# Cameras.net
KiCad netlist of a schematic drawn in Altium Designer
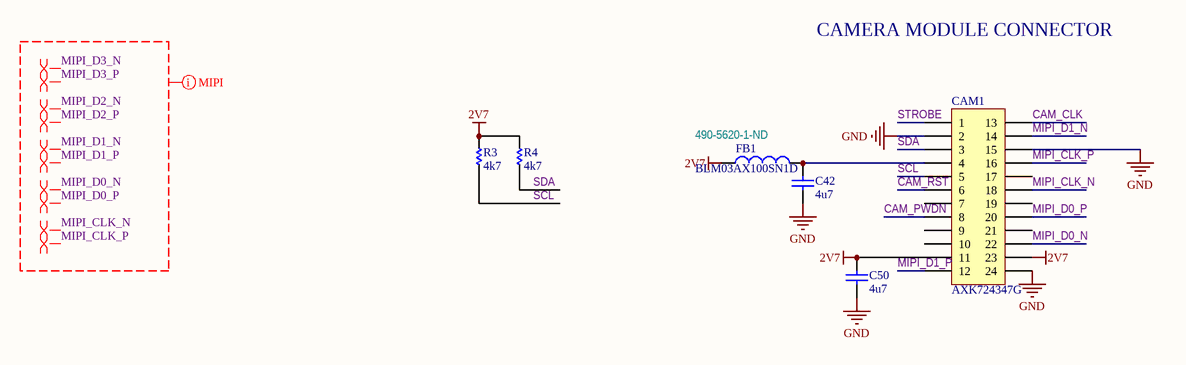
[diagram p0: Cameras.SchDoc]

(export (version "E")
  (design (tool "Eeschema 10.0.6"))
  (components
    (comp (ref "C42")
      (value "4u7")
      (footprint "CAPC1005N")
      (description "Capacitor (Semiconductor SIM Model)")
      (fields (field (name "PUBLISHER") "Altium Limited"))
      (libsource (lib "Miscellaneous Devices") (part "Cap Semi"))
    )
    (comp (ref "C50")
      (value "4u7")
      (footprint "CAPC1005N")
      (description "Capacitor (Semiconductor SIM Model)")
      (fields (field (name "PUBLISHER") "Altium Limited"))
      (libsource (lib "Miscellaneous Devices") (part "Cap Semi"))
    )
    (comp (ref "CAM1")
      (value "AXK724347G")
      (footprint "LI-OV5640-MIPI-AF")
      (description "Header, 12-Pin, Dual row")
      (fields (field (name "PUBLISHER") "Altium Limited"))
      (libsource (lib "Miscellaneous Connectors") (part "Header 12X2A"))
    )
    (comp (ref "FB1")
      (value "BLM03AX100SN1D")
      (footprint "1608[0603]")
      (description "Inductor")
      (fields
        (field (name "SUPPLIER PART NUMBER 1") "490-5620-1-ND")
        (field (name "PUBLISHER") "Altium Limited")
      )
      (libsource (lib "Miscellaneous Devices") (part "Inductor"))
    )
    (comp (ref "R3")
      (value "4k7")
      (footprint "RESC0603N")
      (description "Semiconductor Resistor")
      (fields (field (name "PUBLISHER") "Altium Limited"))
      (libsource (lib "Miscellaneous Devices") (part "Res Semi"))
    )
    (comp (ref "R4")
      (value "4k7")
      (footprint "RESC0603N")
      (description "Semiconductor Resistor")
      (fields (field (name "PUBLISHER") "Altium Limited"))
      (libsource (lib "Miscellaneous Devices") (part "Res Semi"))
    )
  )
  (nets
    (net (code "1") (name "/CAM_CLK") (class "Default")
      (node (ref "CAM1") (pin "13") (pinfunction "13_13") (pintype "passive"))
    )
    (net (code "2") (name "/CAM_PWDN") (class "Default")
      (node (ref "CAM1") (pin "8") (pinfunction "8_8") (pintype "passive"))
    )
    (net (code "3") (name "/CAM_RST") (class "Default")
      (node (ref "CAM1") (pin "6") (pinfunction "6_6") (pintype "passive"))
    )
    (net (code "4") (name "/MIPI_CLK_N") (class "Default")
      (node (ref "CAM1") (pin "18") (pinfunction "18_18") (pintype "passive"))
    )
    (net (code "5") (name "/MIPI_CLK_P") (class "Default")
      (node (ref "CAM1") (pin "16") (pinfunction "16_16") (pintype "passive"))
    )
    (net (code "6") (name "/MIPI_D0_N") (class "Default")
      (node (ref "CAM1") (pin "22") (pinfunction "22_22") (pintype "passive"))
    )
    (net (code "7") (name "/MIPI_D0_P") (class "Default")
      (node (ref "CAM1") (pin "20") (pinfunction "20_20") (pintype "passive"))
    )
    (net (code "8") (name "/MIPI_D1_N") (class "Default")
      (node (ref "CAM1") (pin "14") (pinfunction "14_14") (pintype "passive"))
    )
    (net (code "9") (name "/MIPI_D1_P") (class "Default")
      (node (ref "CAM1") (pin "12") (pinfunction "12_12") (pintype "passive"))
    )
    (net (code "14") (name "/SCL") (class "Default")
      (node (ref "CAM1") (pin "5") (pinfunction "5_5") (pintype "passive"))
      (node (ref "R3") (pin "1") (pinfunction "1_1") (pintype "passive"))
    )
    (net (code "15") (name "/SDA") (class "Default")
      (node (ref "CAM1") (pin "3") (pinfunction "3_3") (pintype "passive"))
      (node (ref "R4") (pin "1") (pinfunction "1_1") (pintype "passive"))
    )
    (net (code "16") (name "/STROBE") (class "Default")
      (node (ref "CAM1") (pin "1") (pinfunction "1_1") (pintype "passive"))
    )
    (net (code "17") (name "2V7") (class "Default")
      (node (ref "C50") (pin "2") (pinfunction "2_2") (pintype "passive"))
      (node (ref "CAM1") (pin "11") (pinfunction "11_11") (pintype "passive"))
      (node (ref "CAM1") (pin "23") (pinfunction "23_23") (pintype "passive"))
      (node (ref "FB1") (pin "1") (pinfunction "1_1") (pintype "passive"))
      (node (ref "R3") (pin "2") (pinfunction "2_2") (pintype "passive"))
      (node (ref "R4") (pin "2") (pinfunction "2_2") (pintype "passive"))
    )
    (net (code "18") (name "GND") (class "Default")
      (node (ref "C42") (pin "1") (pinfunction "1_1") (pintype "passive"))
      (node (ref "C50") (pin "1") (pinfunction "1_1") (pintype "passive"))
      (node (ref "CAM1") (pin "15") (pinfunction "15_15") (pintype "passive"))
      (node (ref "CAM1") (pin "2") (pinfunction "2_2") (pintype "passive"))
      (node (ref "CAM1") (pin "24") (pinfunction "24_24") (pintype "passive"))
    )
    (net (code "19") (name "Net-(C42-Pad2)") (class "Default")
      (node (ref "C42") (pin "2") (pinfunction "2_2") (pintype "passive"))
      (node (ref "CAM1") (pin "4") (pinfunction "4_4") (pintype "passive"))
      (node (ref "FB1") (pin "2") (pinfunction "2_2") (pintype "passive"))
    )
    (net (code "20") (name "unconnected-(CAM1-Pad7)") (class "Default")
      (node (ref "CAM1") (pin "7") (pinfunction "7_7") (pintype "passive"))
    )
    (net (code "21") (name "unconnected-(CAM1-Pad9)") (class "Default")
      (node (ref "CAM1") (pin "9") (pinfunction "9_9") (pintype "passive"))
    )
    (net (code "22") (name "unconnected-(CAM1-Pad10)") (class "Default")
      (node (ref "CAM1") (pin "10") (pinfunction "10_10") (pintype "passive"))
    )
    (net (code "23") (name "unconnected-(CAM1-Pad17)") (class "Default")
      (node (ref "CAM1") (pin "17") (pinfunction "17_17") (pintype "passive"))
    )
    (net (code "24") (name "unconnected-(CAM1-Pad19)") (class "Default")
      (node (ref "CAM1") (pin "19") (pinfunction "19_19") (pintype "passive"))
    )
    (net (code "25") (name "unconnected-(CAM1-Pad21)") (class "Default")
      (node (ref "CAM1") (pin "21") (pinfunction "21_21") (pintype "passive"))
    )
  )
)
